# HamsterLabsPhotoInterruptor2.net
KiCad netlist of a schematic drawn in EAGLE
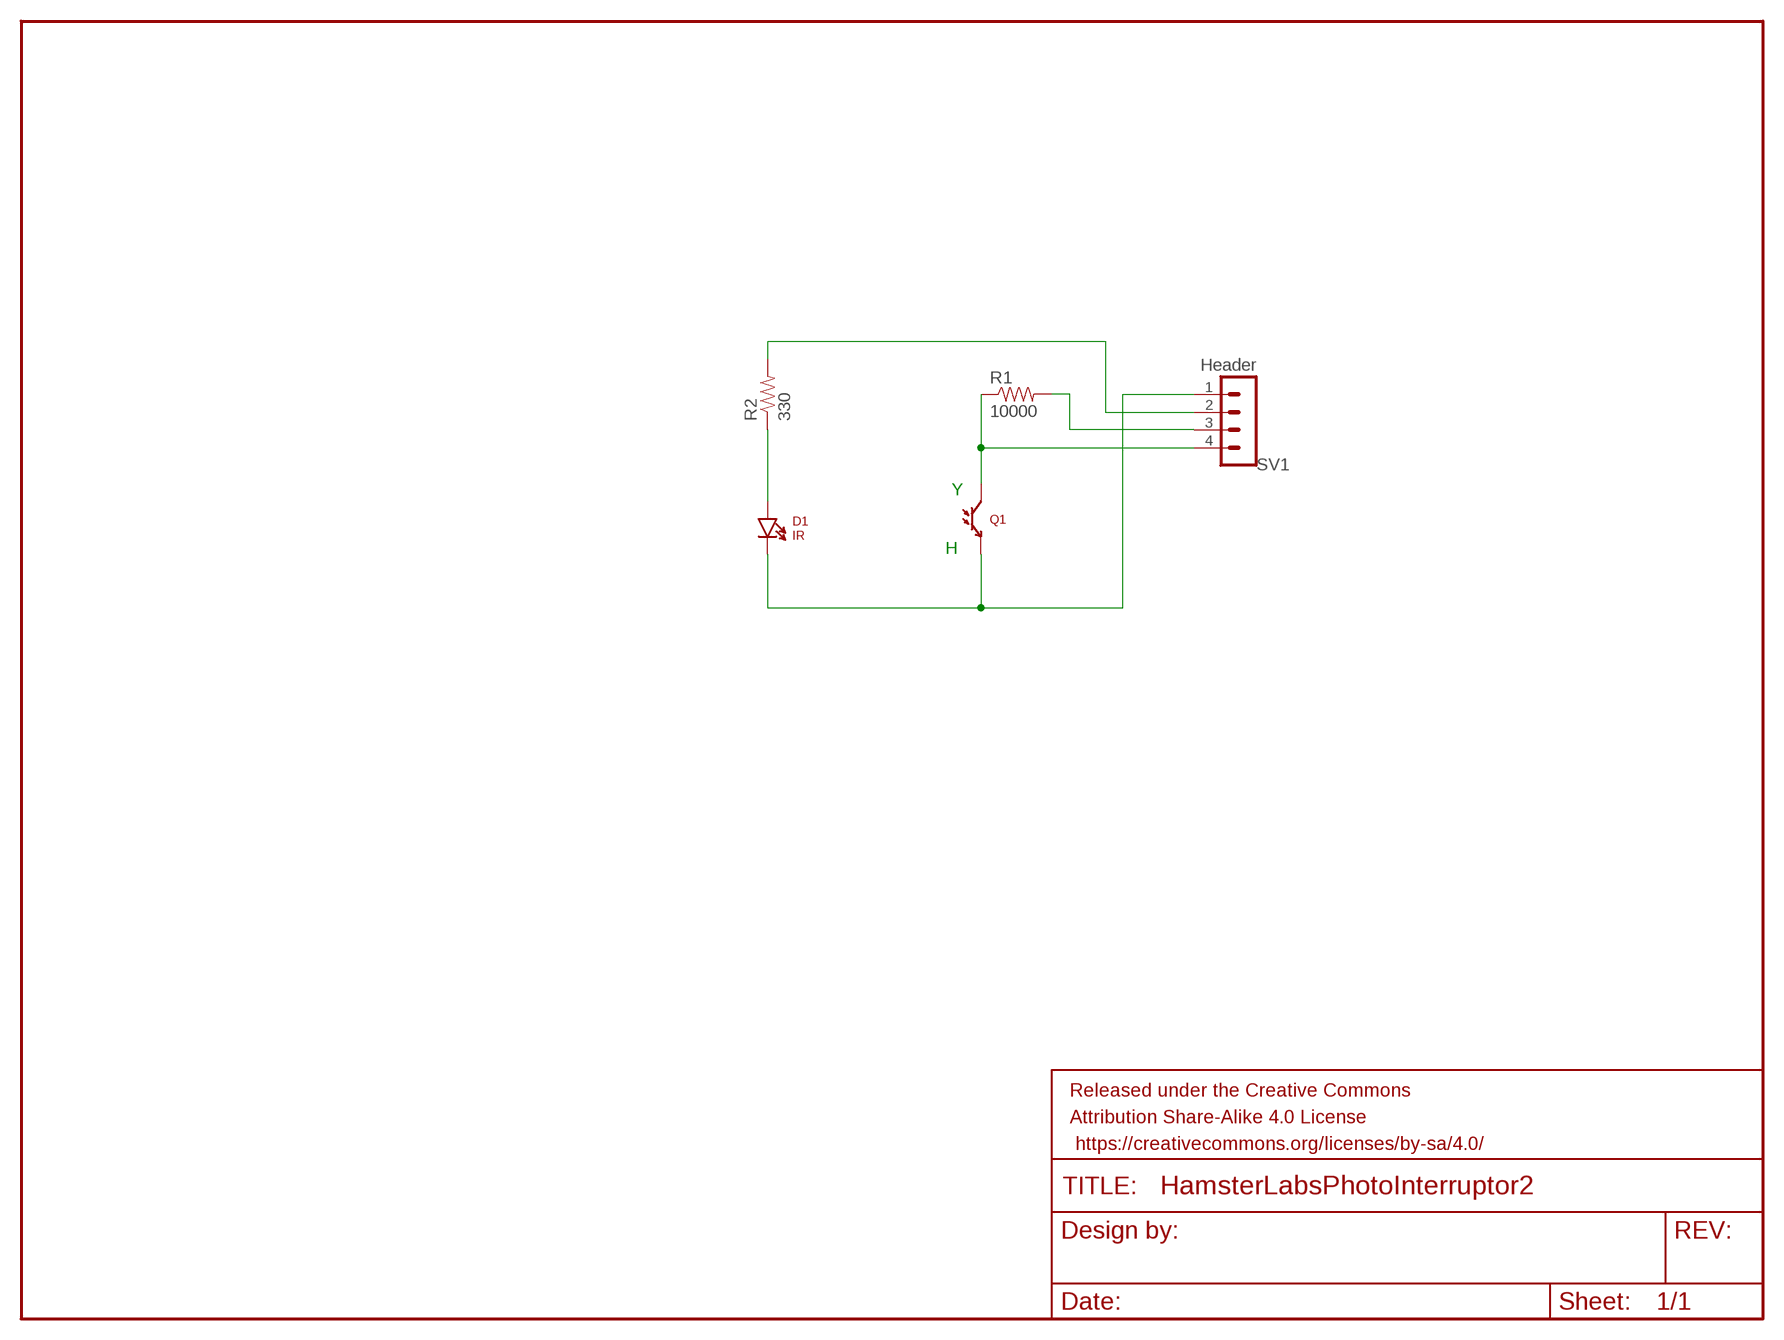
[diagram p0: schematic, sheet 1]

(export (version "E")
  (design (tool "Eeschema 10.0.6"))
  (components
    (comp (ref "D1")
      (value "IR")
      (footprint "eagle-import:LTE-302")
      (libsource (lib "eagle-import") (part "LTE-302"))
    )
    (comp (ref "FRAME1")
      (value "FRAME-LETTERNO_PACKAGE")
      (footprint "eagle-import:DUMMY")
      (fields (field (name "DESIGNER") "Nobody"))
      (libsource (lib "eagle-import") (part "FRAME-LETTERNO_PACKAGE"))
    )
    (comp (ref "Q1")
      (value "LTR-301")
      (footprint "eagle-import:LTR-301")
      (libsource (lib "eagle-import") (part "LTR-301"))
    )
    (comp (ref "R1")
      (value "10000")
      (footprint "eagle-import:AXIAL-0.3")
      (libsource (lib "eagle-import") (part "10KOHM-1/4W-1%(PTH)HORIZ"))
    )
    (comp (ref "R2")
      (value "330")
      (footprint "eagle-import:AXIAL-0.3")
      (libsource (lib "eagle-import") (part "10KOHM-1/4W-1%(PTH)HORIZ"))
    )
    (comp (ref "SV1")
      (value "Header")
      (footprint "eagle-import:MA04-1")
      (libsource (lib "eagle-import") (part "MA04-1"))
    )
  )
  (nets
    (net (code "1") (name "Net-(D1-PadC)") (class "Default")
      (node (ref "D1") (pin "C") (pinfunction "C_C") (pintype "bidirectional"))
      (node (ref "Q1") (pin "E") (pinfunction "E_E") (pintype "bidirectional"))
      (node (ref "SV1") (pin "1") (pinfunction "1_1") (pintype "passive"))
    )
    (net (code "2") (name "Net-(R1-1)") (class "Default")
      (node (ref "Q1") (pin "C") (pinfunction "C_C") (pintype "bidirectional"))
      (node (ref "R1") (pin "P$1") (pinfunction "1_P$1") (pintype "passive"))
      (node (ref "SV1") (pin "4") (pinfunction "4_4") (pintype "passive"))
    )
    (net (code "3") (name "Net-(R1-2)") (class "Default")
      (node (ref "R1") (pin "P$2") (pinfunction "2_P$2") (pintype "passive"))
      (node (ref "SV1") (pin "3") (pinfunction "3_3") (pintype "passive"))
    )
    (net (code "4") (name "Net-(R2-1)") (class "Default")
      (node (ref "D1") (pin "A") (pinfunction "A_A") (pintype "bidirectional"))
      (node (ref "R2") (pin "P$1") (pinfunction "1_P$1") (pintype "passive"))
    )
    (net (code "5") (name "Net-(R2-2)") (class "Default")
      (node (ref "R2") (pin "P$2") (pinfunction "2_P$2") (pintype "passive"))
      (node (ref "SV1") (pin "2") (pinfunction "2_2") (pintype "passive"))
    )
  )
)
